# TempX.net
KiCad netlist of a schematic drawn in EAGLE
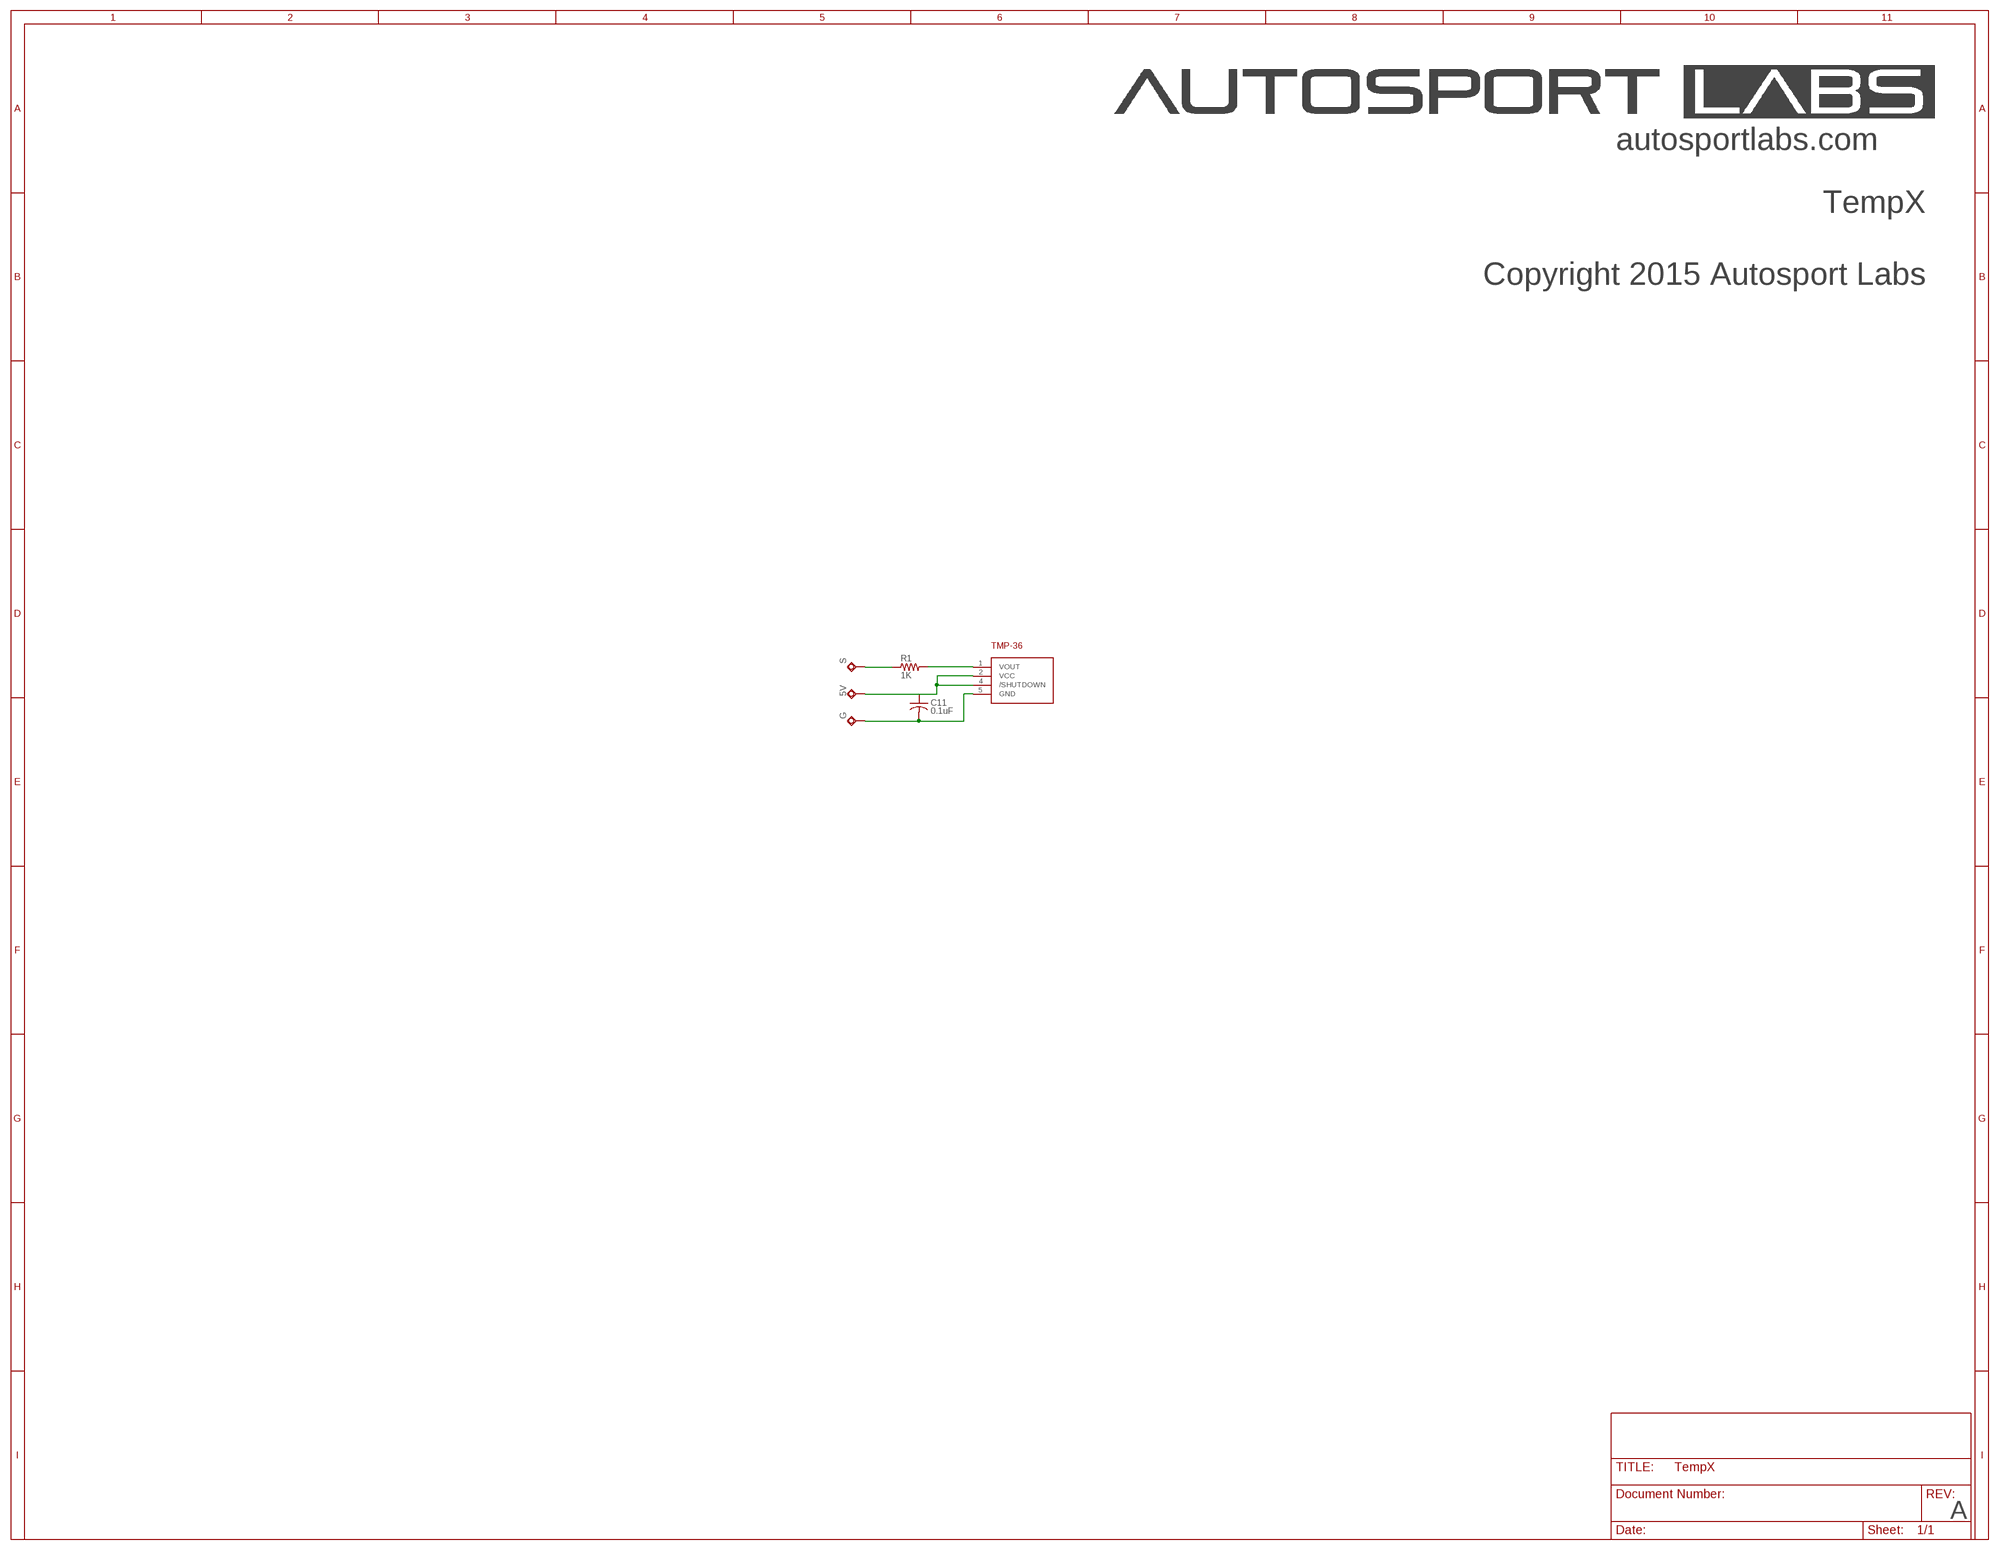
[diagram p0: schematic, sheet 1]

(export (version "E")
  (design (tool "Eeschema 10.0.6"))
  (components
    (comp (ref "5V")
      (value "TPSQPAD1-17")
      (footprint "eagle-import:P1-17")
      (libsource (lib "eagle-import") (part "TPSQPAD1-17"))
    )
    (comp (ref "C11")
      (value "0.1uF")
      (footprint "eagle-import:C0603")
      (libsource (lib "eagle-import") (part "C-USC0603"))
    )
    (comp (ref "G")
      (value "TPSQPAD1-17")
      (footprint "eagle-import:P1-17")
      (libsource (lib "eagle-import") (part "TPSQPAD1-17"))
    )
    (comp (ref "R1")
      (value "1K")
      (footprint "eagle-import:R0603")
      (libsource (lib "eagle-import") (part "R-US_R0603"))
    )
    (comp (ref "S")
      (value "TPSQPAD1-17")
      (footprint "eagle-import:P1-17")
      (libsource (lib "eagle-import") (part "TPSQPAD1-17"))
    )
    (comp (ref "U1")
      (value "TMP36")
      (footprint "eagle-import:SOT-23")
      (libsource (lib "eagle-import") (part "TMP36"))
    )
  )
  (nets
    (net (code "1") (name "Net-(R1-Pad1)") (class "Default")
      (node (ref "R1") (pin "1") (pinfunction "1_1") (pintype "passive"))
      (node (ref "S") (pin "TP") (pinfunction "TP_TP") (pintype "input"))
    )
    (net (code "2") (name "Net-(U1-GND)") (class "Default")
      (node (ref "C11") (pin "2") (pinfunction "2_2") (pintype "passive"))
      (node (ref "G") (pin "TP") (pinfunction "TP_TP") (pintype "input"))
      (node (ref "U1") (pin "5") (pinfunction "GND_5") (pintype "bidirectional"))
    )
    (net (code "3") (name "Net-(U1-VCC)") (class "Default")
      (node (ref "5V") (pin "TP") (pinfunction "TP_TP") (pintype "input"))
      (node (ref "C11") (pin "1") (pinfunction "1_1") (pintype "passive"))
      (node (ref "U1") (pin "2") (pinfunction "VCC_2") (pintype "bidirectional"))
      (node (ref "U1") (pin "4") (pinfunction "/SHUTDOWN_4") (pintype "bidirectional"))
    )
    (net (code "4") (name "Net-(U1-VOUT)") (class "Default")
      (node (ref "R1") (pin "2") (pinfunction "2_2") (pintype "passive"))
      (node (ref "U1") (pin "1") (pinfunction "VOUT_1") (pintype "bidirectional"))
    )
  )
)
